# SCH_hack-card_2024-04-07.net
KiCad netlist of a schematic drawn in EasyEDA
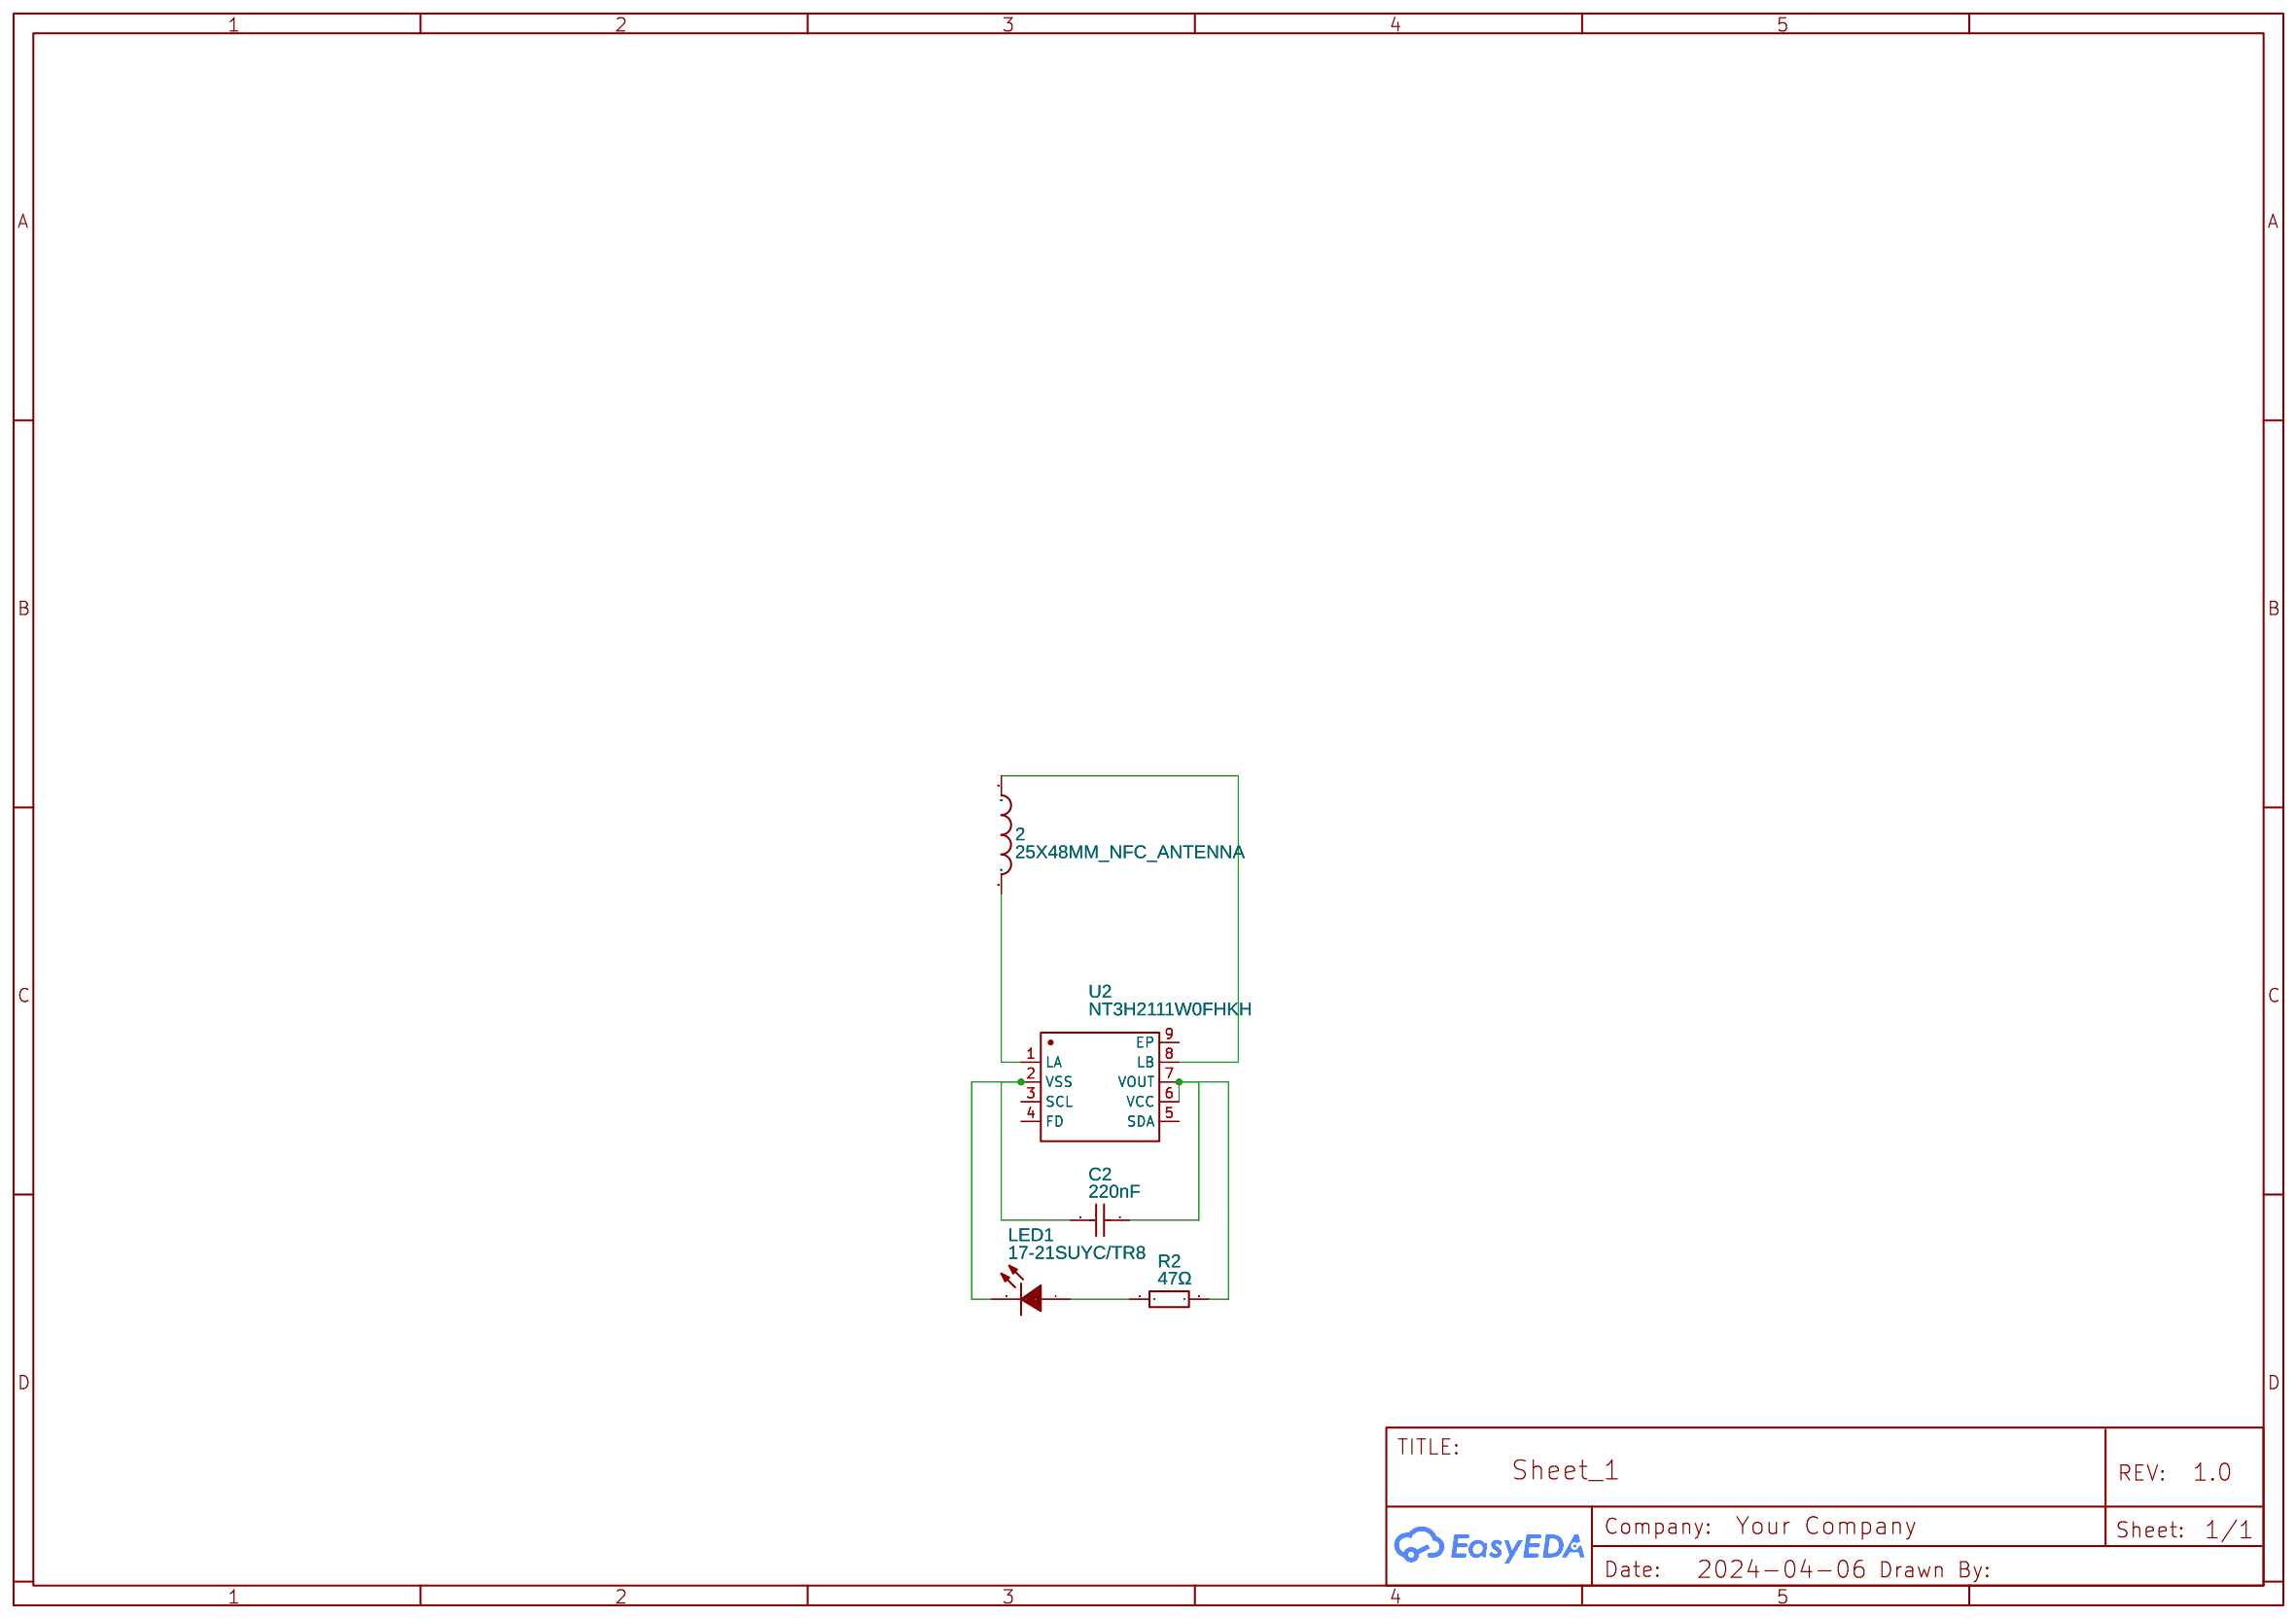
[diagram p0: schematic sheet]

(export (version "E")
  (design (tool "Eeschema 10.0.6"))
  (components
    (comp (ref "2") (value "25X48MM_NFC_ANTENNA") (libsource (lib "") (part "25X48MM_NFC_ANTENNA")))
    (comp (ref "C2")
      (value "220nF")
      (fields
        (field (name "Manufacturer Part") "CL10B224KA8NNNC")
        (field (name "Manufacturer") "SAMSUNG(三星)")
      )
      (libsource (lib "") (part "CL10B224KA8NNNC"))
    )
    (comp (ref "LED1")
      (value "17-21SUYC/TR8")
      (fields (field (name "Manufacturer Part") "KT-0805黄灯") (field (name "Manufacturer") "KENTO"))
      (libsource (lib "") (part "17-21SUYC/TR8"))
    )
    (comp (ref "R2")
      (value "47Ω")
      (fields
        (field (name "Manufacturer Part") "0603WAF470JT5E")
        (field (name "Manufacturer") "UNI-ROYAL(厚声)")
      )
      (libsource (lib "") (part "0603WAF470JT5E"))
    )
    (comp (ref "U2")
      (value "NT3H2111W0FHKH")
      (fields (field (name "Manufacturer") "NXP(恩智浦)"))
      (libsource (lib "") (part "NT3H2111W0FHKH"))
    )
  )
  (nets
    (net (code "1") (name "Net-(LED1-+)") (class "Default")
      (node (ref "LED1") (pin "1") (pinfunction "+_1") (pintype "unspecified"))
      (node (ref "R2") (pin "1") (pinfunction "1_1") (pintype "input"))
    )
    (net (code "2") (name "Net-(LED1--)") (class "Default")
      (node (ref "C2") (pin "1") (pinfunction "1_1") (pintype "input"))
      (node (ref "LED1") (pin "2") (pinfunction "-_2") (pintype "unspecified"))
      (node (ref "U2") (pin "2") (pinfunction "VSS_2") (pintype "unspecified"))
    )
    (net (code "3") (name "Net-(U2-LA)") (class "Default")
      (node (ref "2") (pin "P$2") (pinfunction "P$2_P$2") (pintype "bidirectional"))
      (node (ref "U2") (pin "1") (pinfunction "LA_1") (pintype "unspecified"))
    )
    (net (code "4") (name "Net-(U2-LB)") (class "Default")
      (node (ref "2") (pin "P$1") (pinfunction "P$1_P$1") (pintype "bidirectional"))
      (node (ref "U2") (pin "8") (pinfunction "LB_8") (pintype "unspecified"))
    )
    (net (code "5") (name "Net-(U2-VCC)") (class "Default")
      (node (ref "C2") (pin "2") (pinfunction "2_2") (pintype "input"))
      (node (ref "R2") (pin "2") (pinfunction "2_2") (pintype "input"))
      (node (ref "U2") (pin "6") (pinfunction "VCC_6") (pintype "unspecified"))
      (node (ref "U2") (pin "7") (pinfunction "VOUT_7") (pintype "unspecified"))
    )
    (net (code "6") (name "unconnected-(U2-EP-Pad9)") (class "Default")
      (node (ref "U2") (pin "9") (pinfunction "EP_9") (pintype "unspecified"))
    )
    (net (code "7") (name "unconnected-(U2-FD-Pad4)") (class "Default")
      (node (ref "U2") (pin "4") (pinfunction "FD_4") (pintype "unspecified"))
    )
    (net (code "8") (name "unconnected-(U2-SCL-Pad3)") (class "Default")
      (node (ref "U2") (pin "3") (pinfunction "SCL_3") (pintype "unspecified"))
    )
    (net (code "9") (name "unconnected-(U2-SDA-Pad5)") (class "Default")
      (node (ref "U2") (pin "5") (pinfunction "SDA_5") (pintype "unspecified"))
    )
  )
)
